# MCU.net
KiCad netlist of a schematic drawn in Altium Designer
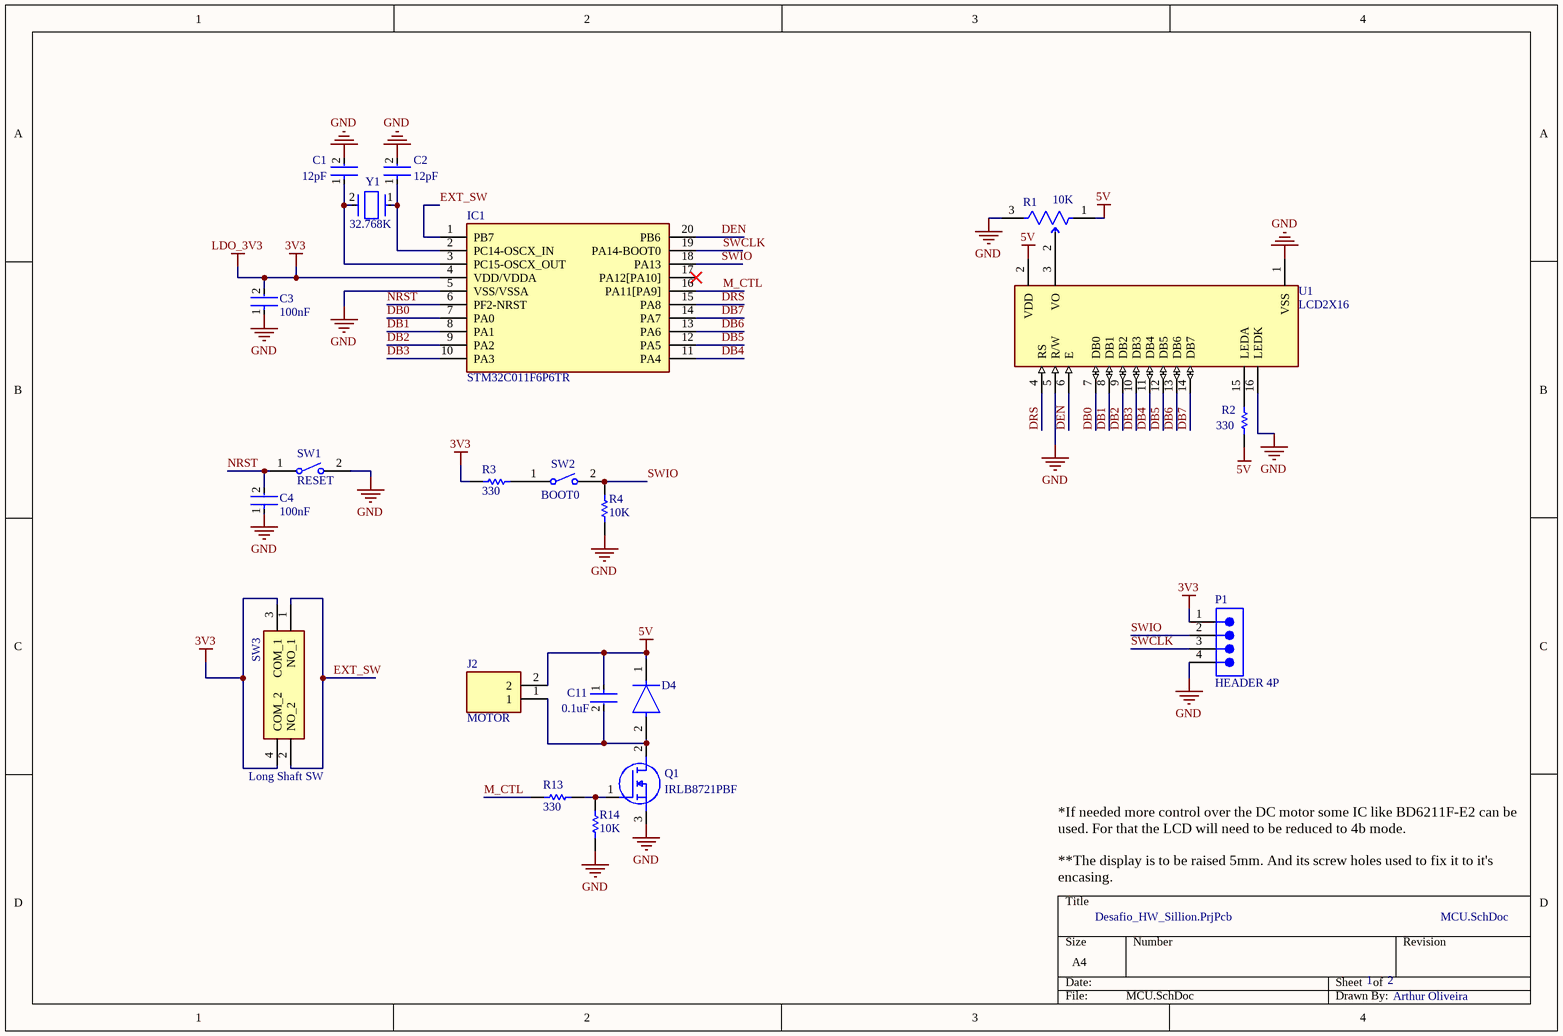
[diagram p0: MCU.SchDoc]

(export (version "E")
  (design (tool "Eeschema 10.0.6"))
  (components
    (comp (ref "C1")
      (value "12pF")
      (footprint "FP-C0603C-CF-MFG")
      (description "Ceramic Capacitor 12Pf 50V, C0G, 5%, 0603, Full Reel")
      (fields (field (name "MANUFACTURER") "KEMET") (field (name "TOLERANCE") "0.05"))
      (libsource (lib "Altium Content Vault") (part "b4654b650e69147ec39a6b967a45e02"))
    )
    (comp (ref "C2")
      (value "12pF")
      (footprint "FP-C0603C-CF-MFG")
      (description "Ceramic Capacitor 12Pf 50V, C0G, 5%, 0603, Full Reel")
      (fields (field (name "MANUFACTURER") "KEMET") (field (name "TOLERANCE") "0.05"))
      (libsource (lib "Altium Content Vault") (part "b4654b650e69147ec39a6b967a45e02"))
    )
    (comp (ref "C3")
      (value "100nF")
      (footprint "FP-CC0805-0_85-MFG")
      (description "CAP CER 0.1UF 16V X7R 0805")
      (fields
        (field (name "MANUFACTURER PART NUMBER") "CC0805KRX7R7BB104")
        (field (name "MANUFACTURER") "Yageo")
      )
      (libsource (lib "Altium Content Vault") (part "11868f565c42a9108669ba33697ecf6"))
    )
    (comp (ref "C4")
      (value "100nF")
      (footprint "FP-CC0805-0_85-MFG")
      (description "CAP CER 0.1UF 16V X7R 0805")
      (fields
        (field (name "MANUFACTURER PART NUMBER") "CC0805KRX7R7BB104")
        (field (name "MANUFACTURER") "Yageo")
      )
      (libsource (lib "Altium Content Vault") (part "11868f565c42a9108669ba33697ecf6"))
    )
    (comp (ref "C11")
      (value "0.1uF")
      (footprint "FP-C0603-CJ-MFG")
      (description "CAP CER 0.1UF 50V X7R 0603")
      (fields (field (name "MANUFACTURER PART NUMBER") "C0603X104K5RACTU") (field (name "VOLTAGE") "50V"))
      (libsource (lib "Altium Content Vault") (part "11868f565c42a9108669ba33697ecf6"))
    )
    (comp (ref "D4")
      (value "SBRT5A50SA-13")
      (footprint "FP-SMA-MFG")
      (description "DIODE SBR 50V 5A SMA")
      (fields
        (field (name "OCTOPART") "https://octopart.com/sbrt5a50sa-13-diodes+inc.-46962091")
        (field (name "MANUFACTURER") "Diodes Inc.")
      )
      (libsource (lib "Altium Content Vault") (part "d7152d700b627762746794eb795d46e"))
    )
    (comp (ref "IC1")
      (value "STM32C011F6P6TR")
      (footprint "SamacSys:SOP65P640X120-20N")
      (description "Integrated Circuit")
      (fields (field (name "MOUSER PART NUMBER") "511-STM32C011F6P6TR"))
      (libsource (lib "*") (part "STM32C011F6P6TR"))
    )
    (comp (ref "J2")
      (value "MOTOR")
      (footprint "SamacSys:1715022")
      (description "Connector")
      (fields
        (field (name "MANUFACTURER_PART_NUMBER") "1715022")
        (field (name "MOUSER PART NUMBER") "651-1715022")
      )
      (libsource (lib "*") (part "1715022"))
    )
    (comp (ref "P1")
      (value "HEADER 4P")
      (footprint "61300411121")
      (libsource (lib "Altium Content Vault") (part "Header_Male_1R_04P"))
    )
    (comp (ref "Q1")
      (value "IRLB8721PBF")
      (footprint "SamacSys:TO254P483X1016X1994-3P")
      (description "MOSFET (N-Channel)")
      (fields (field (name "MOUSER PART NUMBER") "942-IRLB8721PBF"))
      (libsource (lib "*") (part "IRLB8721PBF"))
    )
    (comp (ref "R1")
      (value "10K")
      (footprint "FP-3314J-1-MFG")
      (description "TRIMMER 10K OHM 0.25W J LEAD TOP")
      (libsource (lib "Altium Content Vault") (part "13357d81287629c2fd191d242cfa50c"))
    )
    (comp (ref "R2")
      (value "330")
      (footprint "RESC2013X60X40LL20T25")
      (fields (field (name "MANUFACTURER") "Panasonic") (field (name "PART NUMBER") "ERA6AEB331V"))
      (libsource (lib "Altium Content Vault") (part "RES"))
    )
    (comp (ref "R3")
      (value "330")
      (footprint "RESC2013X60X40LL20T25")
      (fields (field (name "MANUFACTURER") "Panasonic") (field (name "PART NUMBER") "ERA6AEB331V"))
      (libsource (lib "Altium Content Vault") (part "RES"))
    )
    (comp (ref "R4")
      (value "10K")
      (footprint "RESC2013X60X40LL20T25_A")
      (fields (field (name "TOLERANCE") "0.1%") (field (name "MANUFACTURER") "Panasonic"))
      (libsource (lib "Altium Content Vault") (part "RES-2"))
    )
    (comp (ref "R13")
      (value "330")
      (footprint "RESC2013X60X40LL20T25")
      (fields (field (name "MANUFACTURER") "Panasonic") (field (name "PART NUMBER") "ERA6AEB331V"))
      (libsource (lib "Altium Content Vault") (part "RES"))
    )
    (comp (ref "R14")
      (value "10K")
      (footprint "RESC2013X60X40LL20T25_A")
      (fields (field (name "TOLERANCE") "0.1%") (field (name "MANUFACTURER") "Panasonic"))
      (libsource (lib "Altium Content Vault") (part "RES-2"))
    )
    (comp (ref "SW1")
      (value "RESET")
      (footprint "TECO-FSMSM-2_V")
      (description "FSMSM Push Button Switch, 50 mA, -35 to 85 degC, 2-Pin SMD, RoHS, Bulk")
      (fields (field (name "MANUFACTURER") "TE Connectivity"))
      (libsource (lib "Altium Content Vault") (part "SW-SPST-2_C"))
    )
    (comp (ref "SW2")
      (value "BOOT0")
      (footprint "TECO-FSMSM-2_V")
      (description "FSMSM Push Button Switch, 50 mA, -35 to 85 degC, 2-Pin SMD, RoHS, Bulk")
      (fields (field (name "MANUFACTURER") "TE Connectivity"))
      (libsource (lib "Altium Content Vault") (part "SW-SPST-2_C"))
    )
    (comp (ref "SW3")
      (value "Long Shaft SW")
      (footprint "SamacSys:TS0266130BK160LCRD")
      (description "Integrated Circuit")
      (fields
        (field (name "MANUFACTURER_PART_NUMBER") "TS02-66-130-BK-160-LCR-D")
        (field (name "MOUSER PART NUMBER") "179-TS0266130BK160LC")
      )
      (libsource (lib "*") (part "TS02-66-130-BK-160-LCR-D"))
    )
    (comp (ref "U1")
      (value "LCD2X16")
      (footprint "LCD_LCD2X16")
      (description "Display; Display: LCD 2x16 characters (blue backlight)")
      (libsource (lib "LCD2X16") (part "LCD2X16"))
    )
    (comp (ref "Y1")
      (value "32.768K")
      (footprint "FP-NX3215SA-MFG")
      (description "CRYSTAL 32.7680KHZ 12.5PF SMD")
      (libsource (lib "Altium Content Vault") (part "c23a69dc6c9e2f18f2079038eb95dd1"))
    )
  )
  (nets
    (net (code "1") (name "/DB0") (class "Default")
      (node (ref "IC1") (pin "7") (pinfunction "PA0_7") (pintype "passive"))
      (node (ref "U1") (pin "7") (pinfunction "DB0_7") (pintype "bidirectional"))
    )
    (net (code "2") (name "/DB1") (class "Default")
      (node (ref "IC1") (pin "8") (pinfunction "PA1_8") (pintype "passive"))
      (node (ref "U1") (pin "8") (pinfunction "DB1_8") (pintype "bidirectional"))
    )
    (net (code "3") (name "/DB2") (class "Default")
      (node (ref "IC1") (pin "9") (pinfunction "PA2_9") (pintype "passive"))
      (node (ref "U1") (pin "9") (pinfunction "DB2_9") (pintype "bidirectional"))
    )
    (net (code "4") (name "/DB3") (class "Default")
      (node (ref "IC1") (pin "10") (pinfunction "PA3_10") (pintype "passive"))
      (node (ref "U1") (pin "10") (pinfunction "DB3_10") (pintype "bidirectional"))
    )
    (net (code "5") (name "/DB4") (class "Default")
      (node (ref "IC1") (pin "11") (pinfunction "PA4_11") (pintype "passive"))
      (node (ref "U1") (pin "11") (pinfunction "DB4_11") (pintype "bidirectional"))
    )
    (net (code "6") (name "/DB5") (class "Default")
      (node (ref "IC1") (pin "12") (pinfunction "PA5_12") (pintype "passive"))
      (node (ref "U1") (pin "12") (pinfunction "DB5_12") (pintype "bidirectional"))
    )
    (net (code "7") (name "/DB6") (class "Default")
      (node (ref "IC1") (pin "13") (pinfunction "PA6_13") (pintype "passive"))
      (node (ref "U1") (pin "13") (pinfunction "DB6_13") (pintype "bidirectional"))
    )
    (net (code "8") (name "/DB7") (class "Default")
      (node (ref "IC1") (pin "14") (pinfunction "PA7_14") (pintype "passive"))
      (node (ref "U1") (pin "14") (pinfunction "DB7_14") (pintype "bidirectional"))
    )
    (net (code "9") (name "/DEN") (class "Default")
      (node (ref "IC1") (pin "20") (pinfunction "PB6_20") (pintype "passive"))
      (node (ref "U1") (pin "6") (pinfunction "E_6") (pintype "input"))
    )
    (net (code "10") (name "/DRS") (class "Default")
      (node (ref "IC1") (pin "15") (pinfunction "PA8_15") (pintype "passive"))
      (node (ref "U1") (pin "4") (pinfunction "RS_4") (pintype "input"))
    )
    (net (code "11") (name "/EXT_SW") (class "Default")
      (node (ref "IC1") (pin "1") (pinfunction "PB7_1") (pintype "passive"))
      (node (ref "SW3") (pin "1") (pinfunction "NO_1_1") (pintype "passive"))
      (node (ref "SW3") (pin "2") (pinfunction "NO_2_2") (pintype "passive"))
    )
    (net (code "12") (name "/M_CTL") (class "Default")
      (node (ref "IC1") (pin "16") (pinfunction "PA11[PA9]_16") (pintype "passive"))
      (node (ref "R13") (pin "2") (pinfunction "2_2") (pintype "passive"))
    )
    (net (code "13") (name "/NRST") (class "Default")
      (node (ref "C4") (pin "2") (pinfunction "2_2") (pintype "passive"))
      (node (ref "IC1") (pin "6") (pinfunction "PF2-NRST_6") (pintype "passive"))
      (node (ref "SW1") (pin "1") (pinfunction "1_1") (pintype "passive"))
    )
    (net (code "14") (name "/SWCLK") (class "Default")
      (node (ref "IC1") (pin "19") (pinfunction "PA14-BOOT0_19") (pintype "passive"))
      (node (ref "P1") (pin "3") (pinfunction "3_3") (pintype "passive"))
    )
    (net (code "15") (name "/SWIO") (class "Default")
      (node (ref "IC1") (pin "18") (pinfunction "PA13_18") (pintype "passive"))
      (node (ref "P1") (pin "2") (pinfunction "2_2") (pintype "passive"))
      (node (ref "R4") (pin "2") (pinfunction "2_2") (pintype "passive"))
      (node (ref "SW2") (pin "2") (pinfunction "2_2") (pintype "passive"))
    )
    (net (code "16") (name "3V3") (class "Default")
      (node (ref "C3") (pin "2") (pinfunction "2_2") (pintype "passive"))
      (node (ref "IC1") (pin "4") (pinfunction "VDD/VDDA_4") (pintype "passive"))
      (node (ref "P1") (pin "1") (pinfunction "1_1") (pintype "passive"))
      (node (ref "R3") (pin "2") (pinfunction "2_2") (pintype "passive"))
      (node (ref "SW3") (pin "3") (pinfunction "COM_1_3") (pintype "passive"))
      (node (ref "SW3") (pin "4") (pinfunction "COM_2_4") (pintype "passive"))
    )
    (net (code "17") (name "5V") (class "Default")
      (node (ref "C11") (pin "1") (pinfunction "1_1") (pintype "passive"))
      (node (ref "D4") (pin "1") (pinfunction "C_1") (pintype "passive"))
      (node (ref "J2") (pin "2") (pinfunction "2_2") (pintype "passive"))
      (node (ref "R1") (pin "1") (pinfunction "CCW_1") (pintype "passive"))
      (node (ref "R2") (pin "2") (pinfunction "2_2") (pintype "passive"))
      (node (ref "U1") (pin "2") (pinfunction "VDD_2") (pintype "power_in"))
    )
    (net (code "18") (name "GND") (class "Default")
      (node (ref "C1") (pin "2") (pinfunction "2_2") (pintype "passive"))
      (node (ref "C2") (pin "2") (pinfunction "2_2") (pintype "passive"))
      (node (ref "C3") (pin "1") (pinfunction "1_1") (pintype "passive"))
      (node (ref "C4") (pin "1") (pinfunction "1_1") (pintype "passive"))
      (node (ref "IC1") (pin "5") (pinfunction "VSS/VSSA_5") (pintype "passive"))
      (node (ref "P1") (pin "4") (pinfunction "4_4") (pintype "passive"))
      (node (ref "Q1") (pin "3") (pinfunction "S_3") (pintype "passive"))
      (node (ref "R1") (pin "3") (pinfunction "CW_3") (pintype "passive"))
      (node (ref "R14") (pin "1") (pinfunction "1_1") (pintype "passive"))
      (node (ref "R4") (pin "1") (pinfunction "1_1") (pintype "passive"))
      (node (ref "SW1") (pin "2") (pinfunction "2_2") (pintype "passive"))
      (node (ref "U1") (pin "1") (pinfunction "VSS_1") (pintype "power_in"))
      (node (ref "U1") (pin "16") (pinfunction "LEDK_16") (pintype "passive"))
      (node (ref "U1") (pin "5") (pinfunction "R/W_5") (pintype "input"))
    )
    (net (code "19") (name "Net-(D4-A)") (class "Default")
      (node (ref "C11") (pin "2") (pinfunction "2_2") (pintype "passive"))
      (node (ref "D4") (pin "2") (pinfunction "A_2") (pintype "passive"))
      (node (ref "J2") (pin "1") (pinfunction "1_1") (pintype "passive"))
      (node (ref "Q1") (pin "2") (pinfunction "D_2") (pintype "passive"))
    )
    (net (code "20") (name "Net-(IC1-PC14-OSCX_IN)") (class "Default")
      (node (ref "C2") (pin "1") (pinfunction "1_1") (pintype "passive"))
      (node (ref "IC1") (pin "2") (pinfunction "PC14-OSCX_IN_2") (pintype "passive"))
      (node (ref "Y1") (pin "1") (pinfunction "1_1") (pintype "passive"))
    )
    (net (code "21") (name "Net-(IC1-PC15-OSCX_OUT)") (class "Default")
      (node (ref "C1") (pin "1") (pinfunction "1_1") (pintype "passive"))
      (node (ref "IC1") (pin "3") (pinfunction "PC15-OSCX_OUT_3") (pintype "passive"))
      (node (ref "Y1") (pin "2") (pinfunction "2_2") (pintype "passive"))
    )
    (net (code "22") (name "Net-(Q1-G)") (class "Default")
      (node (ref "Q1") (pin "1") (pinfunction "G_1") (pintype "passive"))
      (node (ref "R13") (pin "1") (pinfunction "1_1") (pintype "passive"))
      (node (ref "R14") (pin "2") (pinfunction "2_2") (pintype "passive"))
    )
    (net (code "23") (name "Net-(R1-WIPER)") (class "Default")
      (node (ref "R1") (pin "2") (pinfunction "WIPER_2") (pintype "passive"))
      (node (ref "U1") (pin "3") (pinfunction "VO_3") (pintype "passive"))
    )
    (net (code "24") (name "Net-(R3-Pad1)") (class "Default")
      (node (ref "R3") (pin "1") (pinfunction "1_1") (pintype "passive"))
      (node (ref "SW2") (pin "1") (pinfunction "1_1") (pintype "passive"))
    )
    (net (code "25") (name "Net-(U1-LEDA)") (class "Default")
      (node (ref "R2") (pin "1") (pinfunction "1_1") (pintype "passive"))
      (node (ref "U1") (pin "15") (pinfunction "LEDA_15") (pintype "passive"))
    )
    (net (code "26") (name "unconnected-(IC1-PA12[PA10]-Pad17)") (class "Default")
      (node (ref "IC1") (pin "17") (pinfunction "PA12[PA10]_17") (pintype "passive+no_connect"))
    )
  )
)
